# sapog_reference_hardware.net
KiCad netlist of a schematic drawn in EAGLE
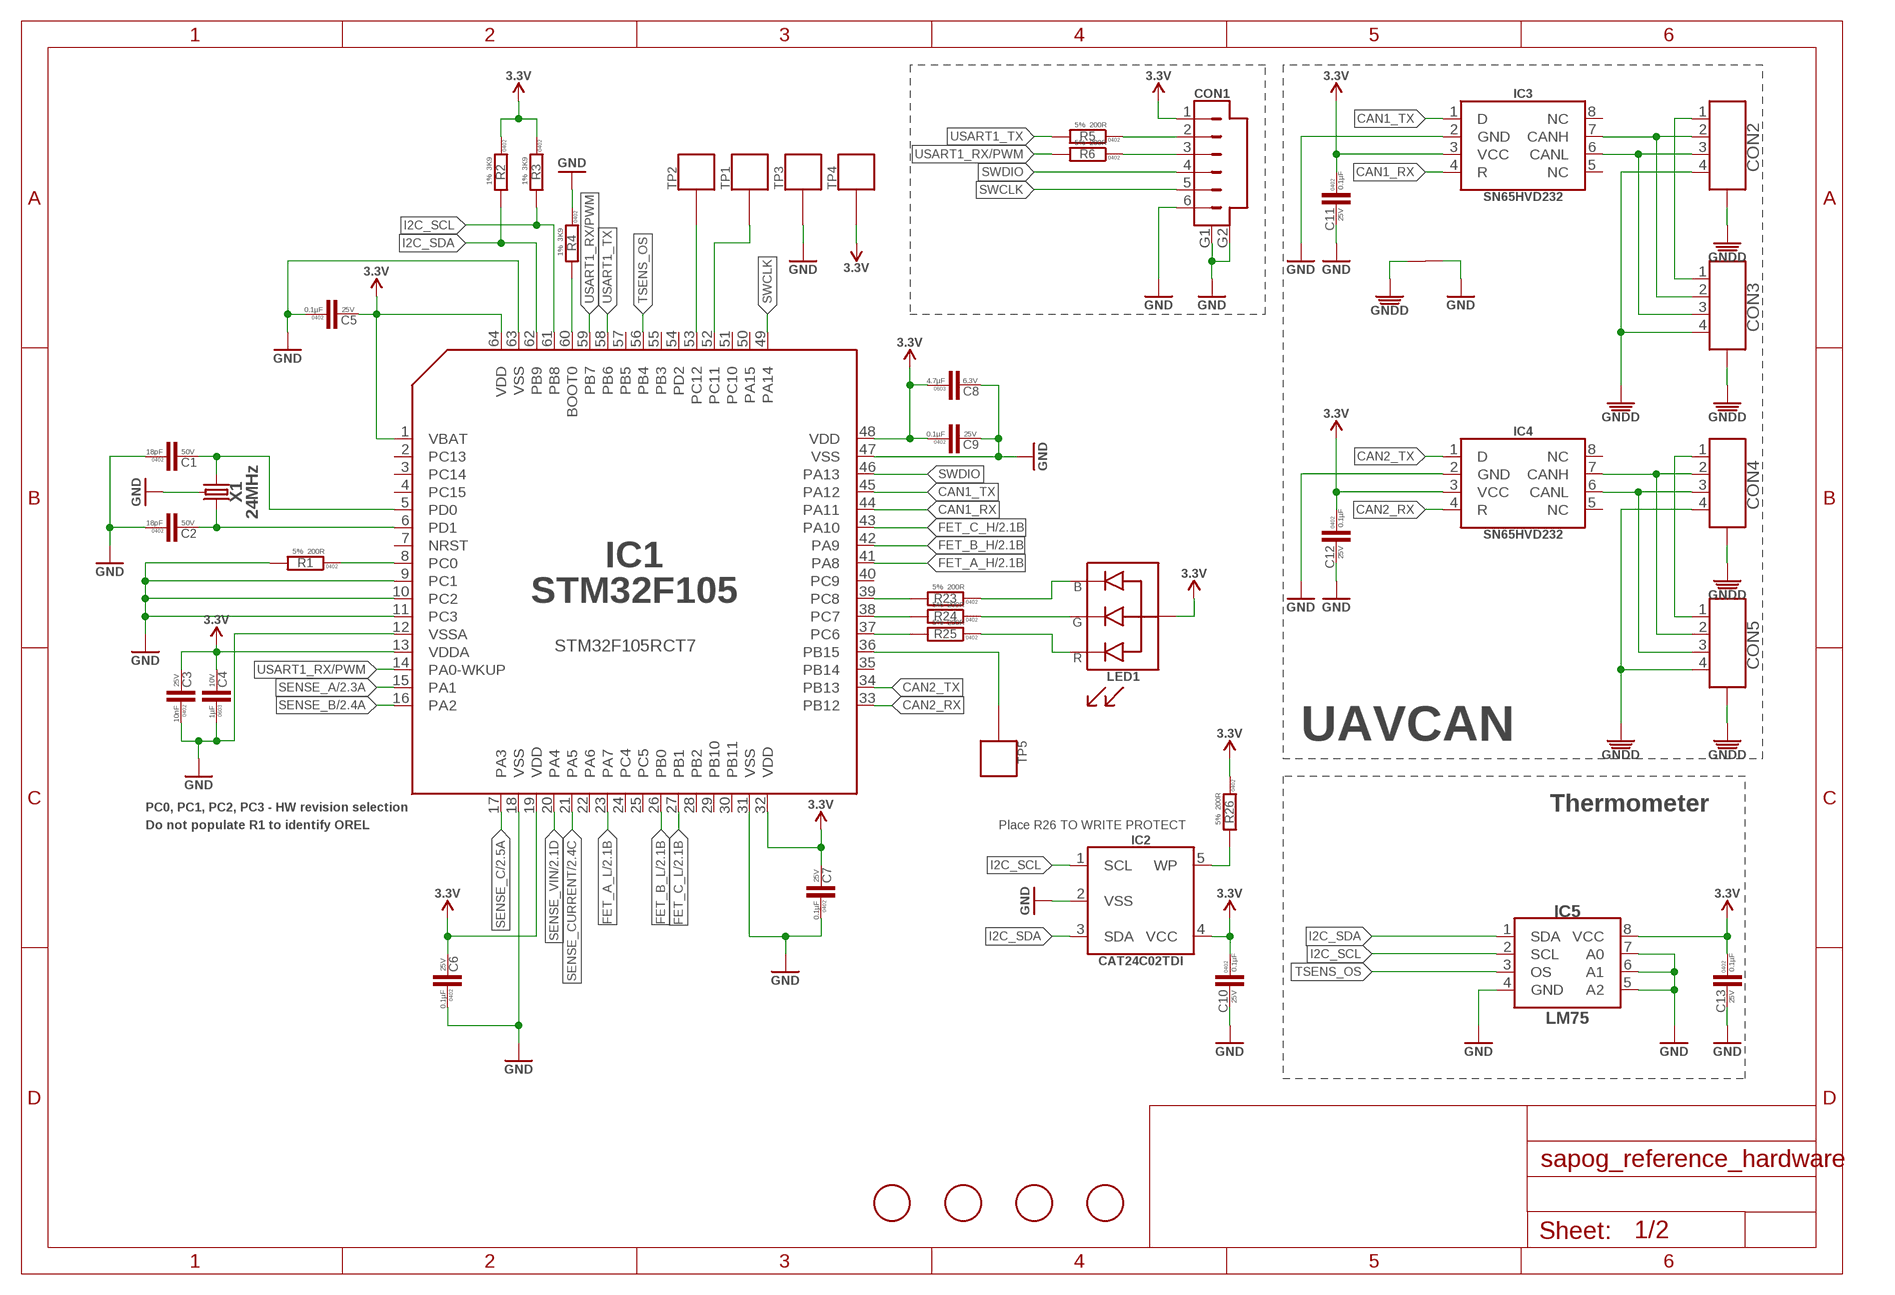
[diagram p0: schematic, sheet 1]
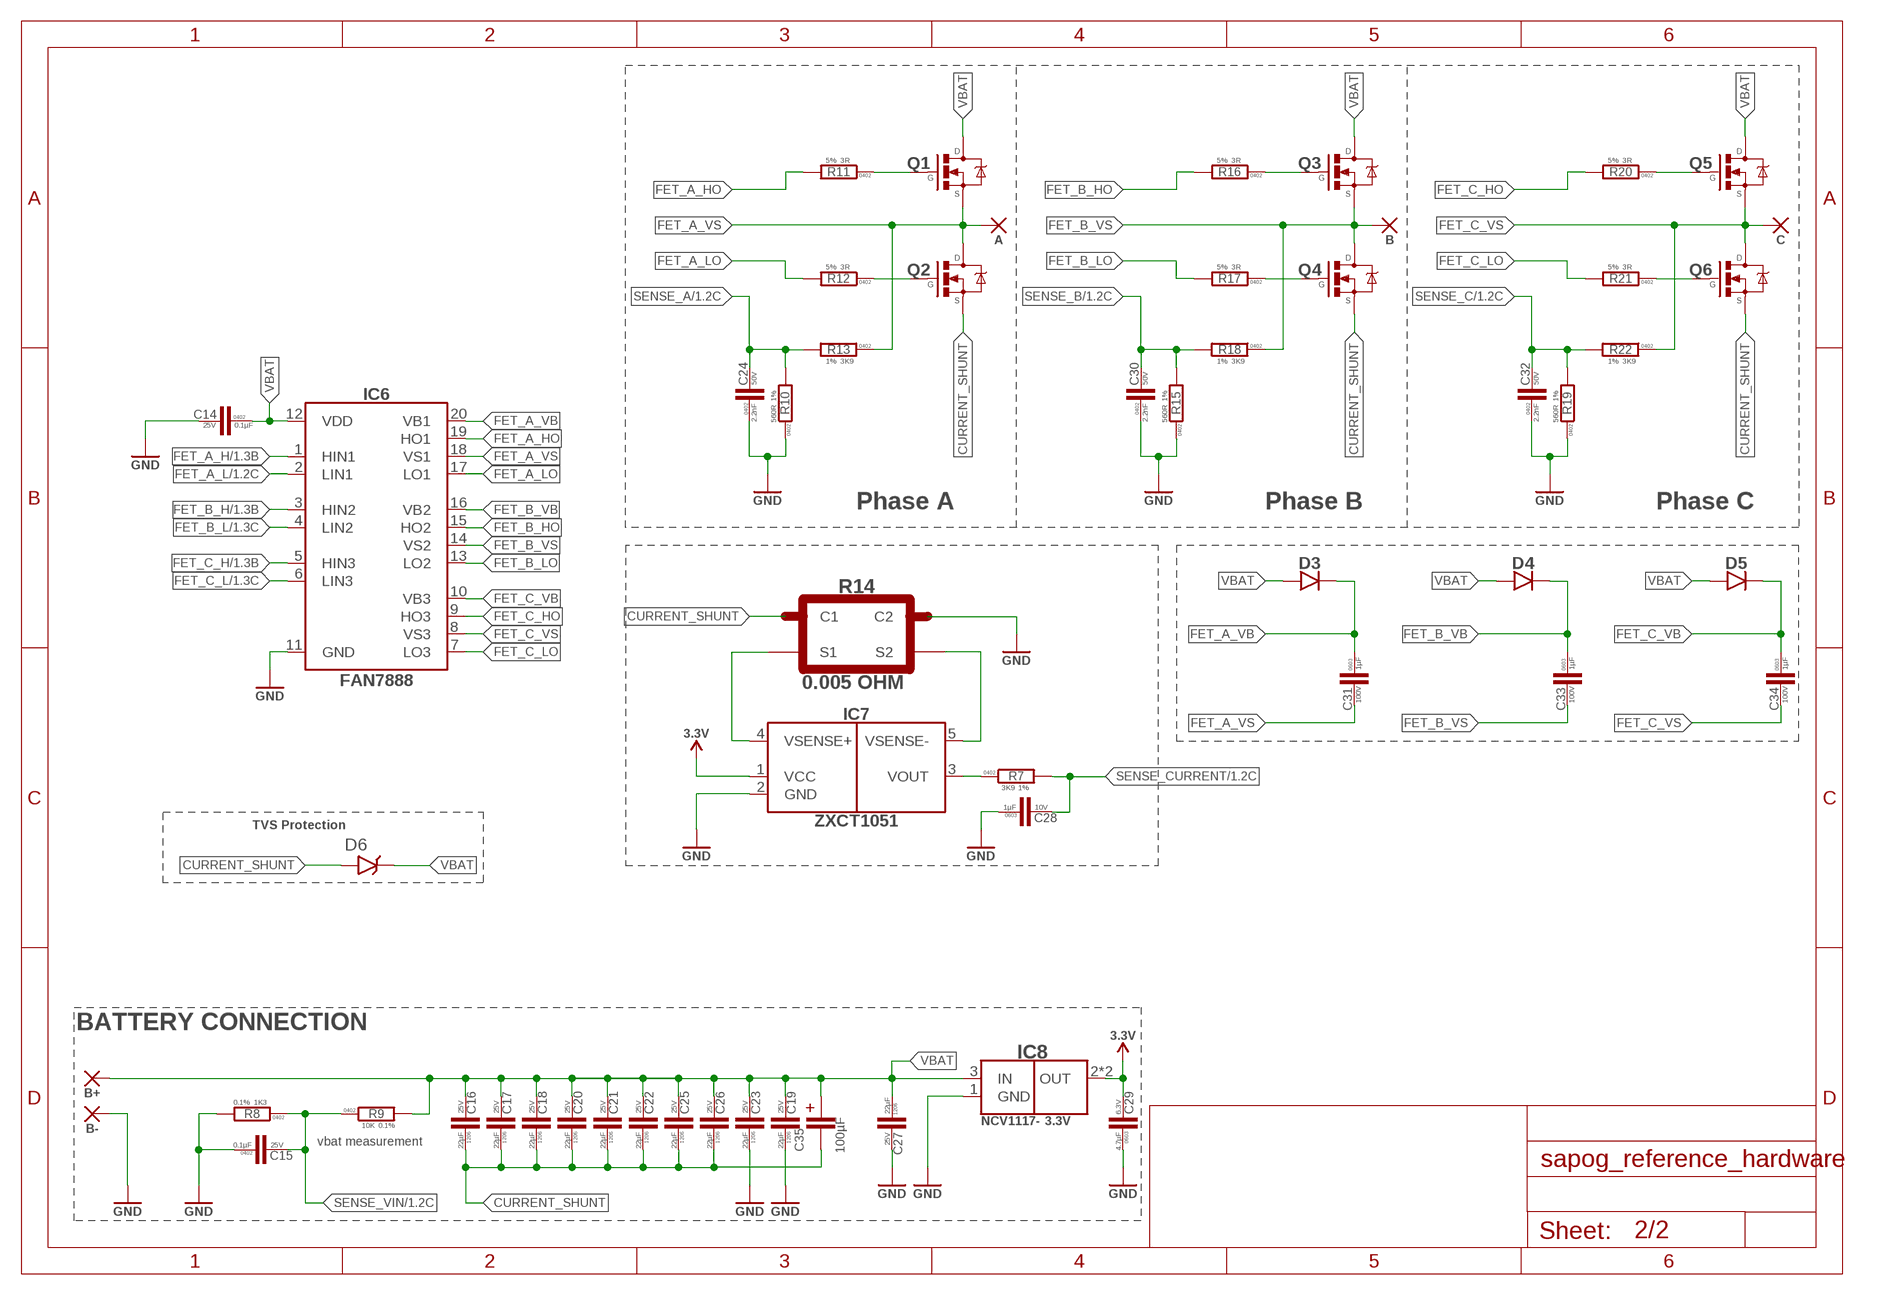
[diagram p1: schematic, sheet 2]

(export (version "E")
  (design (tool "Eeschema 10.0.6"))
  (components
    (comp (ref "C1")
      (value "18pF")
      (footprint "eagle-import:C0402")
      (fields (field (name "MANF") "Kemet") (field (name "TOLERANCE") "+-1%") (field (name "VOLTAGE") "50V"))
      (libsource (lib "eagle-import") (part "18PF-0402-50V_5%_NP0"))
    )
    (comp (ref "C2")
      (value "18pF")
      (footprint "eagle-import:C0402")
      (fields (field (name "MANF") "Kemet") (field (name "TOLERANCE") "+-1%") (field (name "VOLTAGE") "50V"))
      (libsource (lib "eagle-import") (part "18PF-0402-50V_5%_NP0"))
    )
    (comp (ref "C3")
      (value "10nF")
      (footprint "eagle-import:C0402")
      (fields
        (field (name "MANF") "Murata Electronics North America")
        (field (name "TOLERANCE") "+-10%")
        (field (name "VOLTAGE") "25V")
      )
      (libsource (lib "eagle-import") (part "10NF-0402-25V_10%_X7R"))
    )
    (comp (ref "C4")
      (value "1µF")
      (footprint "eagle-import:C0603")
      (fields
        (field (name "MANF") "Taiyo Yuden")
        (field (name "TOLERANCE") "+-10%")
        (field (name "VOLTAGE") "10V")
      )
      (libsource (lib "eagle-import") (part "1µF-0603-10V_10%_X7R"))
    )
    (comp (ref "C5")
      (value "0.1µF")
      (footprint "eagle-import:C0402")
      (fields
        (field (name "MANF") "TDK Corporation")
        (field (name "TOLERANCE") "+-20%")
        (field (name "VOLTAGE") "25V")
      )
      (libsource (lib "eagle-import") (part "0.1µF-0402-25V_20%_X6S"))
    )
    (comp (ref "C6")
      (value "0.1µF")
      (footprint "eagle-import:C0402")
      (fields
        (field (name "MANF") "TDK Corporation")
        (field (name "TOLERANCE") "+-20%")
        (field (name "VOLTAGE") "25V")
      )
      (libsource (lib "eagle-import") (part "0.1µF-0402-25V_20%_X6S"))
    )
    (comp (ref "C7")
      (value "0.1µF")
      (footprint "eagle-import:C0402")
      (fields
        (field (name "MANF") "TDK Corporation")
        (field (name "TOLERANCE") "+-20%")
        (field (name "VOLTAGE") "25V")
      )
      (libsource (lib "eagle-import") (part "0.1µF-0402-25V_20%_X6S"))
    )
    (comp (ref "C8")
      (value "4.7µF")
      (footprint "eagle-import:C0603")
      (fields
        (field (name "MANF") "Samsung Electro-Mechanics America")
        (field (name "TOLERANCE") "+-10%")
        (field (name "VOLTAGE") "6.3V")
      )
      (libsource (lib "eagle-import") (part "4.7µF-0603-6.3V_10%_X7R"))
    )
    (comp (ref "C9")
      (value "0.1µF")
      (footprint "eagle-import:C0402")
      (fields
        (field (name "MANF") "TDK Corporation")
        (field (name "TOLERANCE") "+-20%")
        (field (name "VOLTAGE") "25V")
      )
      (libsource (lib "eagle-import") (part "0.1µF-0402-25V_20%_X6S"))
    )
    (comp (ref "C10")
      (value "0.1µF")
      (footprint "eagle-import:C0402")
      (fields
        (field (name "MANF") "TDK Corporation")
        (field (name "TOLERANCE") "+-20%")
        (field (name "VOLTAGE") "25V")
      )
      (libsource (lib "eagle-import") (part "0.1µF-0402-25V_20%_X6S"))
    )
    (comp (ref "C11")
      (value "0.1µF")
      (footprint "eagle-import:C0402")
      (fields
        (field (name "MANF") "TDK Corporation")
        (field (name "TOLERANCE") "+-20%")
        (field (name "VOLTAGE") "25V")
      )
      (libsource (lib "eagle-import") (part "0.1µF-0402-25V_20%_X6S"))
    )
    (comp (ref "C12")
      (value "0.1µF")
      (footprint "eagle-import:C0402")
      (fields
        (field (name "MANF") "TDK Corporation")
        (field (name "TOLERANCE") "+-20%")
        (field (name "VOLTAGE") "25V")
      )
      (libsource (lib "eagle-import") (part "0.1µF-0402-25V_20%_X6S"))
    )
    (comp (ref "C13")
      (value "0.1µF")
      (footprint "eagle-import:C0402")
      (fields
        (field (name "MANF") "TDK Corporation")
        (field (name "TOLERANCE") "+-20%")
        (field (name "VOLTAGE") "25V")
      )
      (libsource (lib "eagle-import") (part "0.1µF-0402-25V_20%_X6S"))
    )
    (comp (ref "CON1")
      (value "SM06B-SRSS-TB")
      (footprint "eagle-import:SM06B")
      (fields (field (name "MANF") "JST Sales America Inc") (field (name "PARTNO") "SM06B-SRSS-TB"))
      (libsource (lib "eagle-import") (part "SM06B-SRSS-TB"))
    )
    (comp (ref "CON2")
      (value "CON-4P-RA-JST_GH")
      (footprint "eagle-import:JST_GH-4P-RA")
      (fields (field (name "MANF") "JST Sales America Inc"))
      (libsource (lib "eagle-import") (part "CON-4P-RA-JST_GH"))
    )
    (comp (ref "CON3")
      (value "CON-4P-RA-JST_GH")
      (footprint "eagle-import:JST_GH-4P-RA")
      (fields (field (name "MANF") "JST Sales America Inc"))
      (libsource (lib "eagle-import") (part "CON-4P-RA-JST_GH"))
    )
    (comp (ref "CON4")
      (value "CON-4P-RA-JST_GH")
      (footprint "eagle-import:JST_GH-4P-RA")
      (fields (field (name "MANF") "JST Sales America Inc"))
      (libsource (lib "eagle-import") (part "CON-4P-RA-JST_GH"))
    )
    (comp (ref "CON5")
      (value "CON-4P-RA-JST_GH")
      (footprint "eagle-import:JST_GH-4P-RA")
      (fields (field (name "MANF") "JST Sales America Inc"))
      (libsource (lib "eagle-import") (part "CON-4P-RA-JST_GH"))
    )
    (comp (ref "FD1")
      (value "FIDUCIALMOUNT")
      (footprint "eagle-import:FIDUCIA-MOUNT")
      (libsource (lib "eagle-import") (part "FIDUCIALMOUNT"))
    )
    (comp (ref "FD2")
      (value "FIDUCIALMOUNT")
      (footprint "eagle-import:FIDUCIA-MOUNT")
      (libsource (lib "eagle-import") (part "FIDUCIALMOUNT"))
    )
    (comp (ref "FD3")
      (value "FIDUCIALMOUNT")
      (footprint "eagle-import:FIDUCIA-MOUNT")
      (libsource (lib "eagle-import") (part "FIDUCIALMOUNT"))
    )
    (comp (ref "FD4")
      (value "FIDUCIALMOUNT")
      (footprint "eagle-import:FIDUCIA-MOUNT")
      (libsource (lib "eagle-import") (part "FIDUCIALMOUNT"))
    )
    (comp (ref "IC1")
      (value "STM32F105")
      (footprint "eagle-import:TQFP64-10X10")
      (fields
        (field (name "MANF") "STMicroelectronics")
        (field (name "DIGIKEY#") "497-11547-ND")
        (field (name "MANF#") "STM32F105RCT7")
      )
      (libsource (lib "eagle-import") (part "STM32F105"))
    )
    (comp (ref "IC2")
      (value "CAT24C02")
      (footprint "eagle-import:SOT23-5L")
      (fields (field (name "MANF") "ON Semiconductor"))
      (libsource (lib "eagle-import") (part "CAT24C02"))
    )
    (comp (ref "IC3")
      (value "SN65HVD232D")
      (footprint "eagle-import:SOIC8")
      (fields (field (name "MANF") "Texas Instruments"))
      (libsource (lib "eagle-import") (part "SN65HVD232D"))
    )
    (comp (ref "IC4")
      (value "SN65HVD232D")
      (footprint "eagle-import:SOIC8")
      (fields (field (name "MANF") "Texas Instruments"))
      (libsource (lib "eagle-import") (part "SN65HVD232D"))
    )
    (comp (ref "IC5")
      (value "LM75BD-TSSOP8")
      (footprint "eagle-import:TSSOP8")
      (fields (field (name "MANF") "NXP Semiconductors"))
      (libsource (lib "eagle-import") (part "LM75BD-TSSOP8"))
    )
    (comp (ref "LED1")
      (value "LTST-C19HE1WT")
      (footprint "eagle-import:LITE_ON_RGB_LED")
      (libsource (lib "eagle-import") (part "LTST-C19HE1WT"))
    )
    (comp (ref "R1")
      (value "200R")
      (footprint "eagle-import:R0402")
      (fields (field (name "MANF") "Yageo") (field (name "TOLERANCE") "5%"))
      (libsource (lib "eagle-import") (part "200R-0402-5%"))
    )
    (comp (ref "R2")
      (value "3K9")
      (footprint "eagle-import:R0402")
      (fields (field (name "MANF") "Yageo") (field (name "TOLERANCE") "1%"))
      (libsource (lib "eagle-import") (part "3K9-0402-1%"))
    )
    (comp (ref "R3")
      (value "3K9")
      (footprint "eagle-import:R0402")
      (fields (field (name "MANF") "Yageo") (field (name "TOLERANCE") "1%"))
      (libsource (lib "eagle-import") (part "3K9-0402-1%"))
    )
    (comp (ref "R4")
      (value "3K9")
      (footprint "eagle-import:R0402")
      (fields (field (name "MANF") "Yageo") (field (name "TOLERANCE") "1%"))
      (libsource (lib "eagle-import") (part "3K9-0402-1%"))
    )
    (comp (ref "R5")
      (value "200R")
      (footprint "eagle-import:R0402")
      (fields
        (field (name "MANF") "Yageo")
        (field (name "TOLERANCE") "5%")
        (field (name "PARTNO") "RC0402FR-07240RL")
      )
      (libsource (lib "eagle-import") (part "200R-0402-5%"))
    )
    (comp (ref "R6")
      (value "200R")
      (footprint "eagle-import:R0402")
      (fields
        (field (name "MANF") "Yageo")
        (field (name "TOLERANCE") "5%")
        (field (name "PARTNO") "RC0402FR-07240RL")
      )
      (libsource (lib "eagle-import") (part "200R-0402-5%"))
    )
    (comp (ref "R23")
      (value "200R")
      (footprint "eagle-import:R0402")
      (fields
        (field (name "MANF") "Yageo")
        (field (name "TOLERANCE") "5%")
        (field (name "PARTNO") "RC0402FR-07240RL")
      )
      (libsource (lib "eagle-import") (part "200R-0402-5%"))
    )
    (comp (ref "R24")
      (value "200R")
      (footprint "eagle-import:R0402")
      (fields
        (field (name "MANF") "Yageo")
        (field (name "TOLERANCE") "5%")
        (field (name "PARTNO") "RC0402FR-07240RL")
      )
      (libsource (lib "eagle-import") (part "200R-0402-5%"))
    )
    (comp (ref "R25")
      (value "200R")
      (footprint "eagle-import:R0402")
      (fields
        (field (name "MANF") "Yageo")
        (field (name "TOLERANCE") "5%")
        (field (name "PARTNO") "RC0402FR-07240RL")
      )
      (libsource (lib "eagle-import") (part "200R-0402-5%"))
    )
    (comp (ref "R26")
      (value "200R")
      (footprint "eagle-import:R0402")
      (fields
        (field (name "MANF") "Yageo")
        (field (name "TOLERANCE") "5%")
        (field (name "PARTNO") "RC0402FR-07240RL")
      )
      (libsource (lib "eagle-import") (part "200R-0402-5%"))
    )
    (comp (ref "TP1")
      (value "PAD.05")
      (footprint "eagle-import:PAD.05X.05")
      (libsource (lib "eagle-import") (part "PAD.05"))
    )
    (comp (ref "TP2")
      (value "PAD.05")
      (footprint "eagle-import:PAD.05X.05")
      (libsource (lib "eagle-import") (part "PAD.05"))
    )
    (comp (ref "TP3")
      (value "PAD.05")
      (footprint "eagle-import:PAD.05X.05")
      (libsource (lib "eagle-import") (part "PAD.05"))
    )
    (comp (ref "TP4")
      (value "PAD.05")
      (footprint "eagle-import:PAD.05X.05")
      (libsource (lib "eagle-import") (part "PAD.05"))
    )
    (comp (ref "TP5")
      (value "PAD.05")
      (footprint "eagle-import:PAD.05X.05")
      (libsource (lib "eagle-import") (part "PAD.05"))
    )
    (comp (ref "U$2")
      (value "CONNECTION")
      (footprint "eagle-import:CONNECTION")
      (libsource (lib "eagle-import") (part "CONNECTION"))
    )
    (comp (ref "X1")
      (value "24MHz")
      (footprint "eagle-import:OSCILLATOR-3.2X2.5")
      (fields
        (field (name "MANF") "AVX Corp/Kyocera Corp")
        (field (name "DIGIKEY#") "1253-1198-1-ND")
        (field (name "MANF#") "CX3225GB24000P0HPQCC")
      )
      (libsource (lib "eagle-import") (part "CRYSTAL-3.2X2.5-4P"))
    )
    (comp (ref "A")
      (value "WIREPADSMD5-2,5")
      (footprint "eagle-import:5-2,5")
      (libsource (lib "eagle-import") (part "WIREPADSMD5-2,5"))
    )
    (comp (ref "B")
      (value "WIREPADSMD5-2,5")
      (footprint "eagle-import:5-2,5")
      (libsource (lib "eagle-import") (part "WIREPADSMD5-2,5"))
    )
    (comp (ref "B+")
      (value "WIREPADSMD5-2,5")
      (footprint "eagle-import:5-2,5")
      (libsource (lib "eagle-import") (part "WIREPADSMD5-2,5"))
    )
    (comp (ref "B-")
      (value "WIREPADSMD5-2,5")
      (footprint "eagle-import:5-2,5")
      (libsource (lib "eagle-import") (part "WIREPADSMD5-2,5"))
    )
    (comp (ref "C")
      (value "WIREPADSMD5-2,5")
      (footprint "eagle-import:5-2,5")
      (libsource (lib "eagle-import") (part "WIREPADSMD5-2,5"))
    )
    (comp (ref "C14")
      (value "0.1µF")
      (footprint "eagle-import:C0402")
      (fields
        (field (name "MANF") "TDK Corporation")
        (field (name "TOLERANCE") "+-20%")
        (field (name "VOLTAGE") "25V")
      )
      (libsource (lib "eagle-import") (part "0.1µF-0402-25V_20%_X6S"))
    )
    (comp (ref "C15")
      (value "0.1µF")
      (footprint "eagle-import:C0402")
      (fields
        (field (name "MANF") "TDK Corporation")
        (field (name "TOLERANCE") "+-20%")
        (field (name "VOLTAGE") "25V")
      )
      (libsource (lib "eagle-import") (part "0.1µF-0402-25V_20%_X6S"))
    )
    (comp (ref "C16")
      (value "22µF")
      (footprint "eagle-import:C1206")
      (fields
        (field (name "MANF") "Samsung Electro-Mechanics America")
        (field (name "TOLERANCE") "+-10%")
        (field (name "VOLTAGE") "25V")
      )
      (libsource (lib "eagle-import") (part "22µF-1206-25V_10%_X6S"))
    )
    (comp (ref "C17")
      (value "22µF")
      (footprint "eagle-import:C1206")
      (fields
        (field (name "MANF") "Samsung Electro-Mechanics America")
        (field (name "TOLERANCE") "+-10%")
        (field (name "VOLTAGE") "25V")
      )
      (libsource (lib "eagle-import") (part "22µF-1206-25V_10%_X6S"))
    )
    (comp (ref "C18")
      (value "22µF")
      (footprint "eagle-import:C1206")
      (fields
        (field (name "MANF") "Samsung Electro-Mechanics America")
        (field (name "TOLERANCE") "+-10%")
        (field (name "VOLTAGE") "25V")
      )
      (libsource (lib "eagle-import") (part "22µF-1206-25V_10%_X6S"))
    )
    (comp (ref "C19")
      (value "22µF")
      (footprint "eagle-import:C1206")
      (fields
        (field (name "MANF") "Samsung Electro-Mechanics America")
        (field (name "TOLERANCE") "+-10%")
        (field (name "VOLTAGE") "25V")
      )
      (libsource (lib "eagle-import") (part "22µF-1206-25V_10%_X6S"))
    )
    (comp (ref "C20")
      (value "22µF")
      (footprint "eagle-import:C1206")
      (fields
        (field (name "MANF") "Samsung Electro-Mechanics America")
        (field (name "TOLERANCE") "+-10%")
        (field (name "VOLTAGE") "25V")
      )
      (libsource (lib "eagle-import") (part "22µF-1206-25V_10%_X6S"))
    )
    (comp (ref "C21")
      (value "22µF")
      (footprint "eagle-import:C1206")
      (fields
        (field (name "MANF") "Samsung Electro-Mechanics America")
        (field (name "TOLERANCE") "+-10%")
        (field (name "VOLTAGE") "25V")
      )
      (libsource (lib "eagle-import") (part "22µF-1206-25V_10%_X6S"))
    )
    (comp (ref "C22")
      (value "22µF")
      (footprint "eagle-import:C1206")
      (fields
        (field (name "MANF") "Samsung Electro-Mechanics America")
        (field (name "TOLERANCE") "+-10%")
        (field (name "VOLTAGE") "25V")
      )
      (libsource (lib "eagle-import") (part "22µF-1206-25V_10%_X6S"))
    )
    (comp (ref "C23")
      (value "22µF")
      (footprint "eagle-import:C1206")
      (fields
        (field (name "MANF") "Samsung Electro-Mechanics America")
        (field (name "TOLERANCE") "+-10%")
        (field (name "VOLTAGE") "25V")
      )
      (libsource (lib "eagle-import") (part "22µF-1206-25V_10%_X6S"))
    )
    (comp (ref "C24")
      (value "2.2nF")
      (footprint "eagle-import:C0402")
      (fields
        (field (name "MANF") "AVX Corporation")
        (field (name "TOLERANCE") "+-10%")
        (field (name "VOLTAGE") "50V")
      )
      (libsource (lib "eagle-import") (part "2.2NF-0402-50V_10%_X7R"))
    )
    (comp (ref "C25")
      (value "22µF")
      (footprint "eagle-import:C1206")
      (fields
        (field (name "MANF") "Samsung Electro-Mechanics America")
        (field (name "TOLERANCE") "+-10%")
        (field (name "VOLTAGE") "25V")
      )
      (libsource (lib "eagle-import") (part "22µF-1206-25V_10%_X6S"))
    )
    (comp (ref "C26")
      (value "22µF")
      (footprint "eagle-import:C1206")
      (fields
        (field (name "MANF") "Samsung Electro-Mechanics America")
        (field (name "TOLERANCE") "+-10%")
        (field (name "VOLTAGE") "25V")
      )
      (libsource (lib "eagle-import") (part "22µF-1206-25V_10%_X6S"))
    )
    (comp (ref "C27")
      (value "22µF")
      (footprint "eagle-import:C1206")
      (fields
        (field (name "MANF") "Samsung Electro-Mechanics America")
        (field (name "TOLERANCE") "+-10%")
        (field (name "VOLTAGE") "25V")
      )
      (libsource (lib "eagle-import") (part "22µF-1206-25V_10%_X6S"))
    )
    (comp (ref "C28")
      (value "1µF")
      (footprint "eagle-import:C0603")
      (fields
        (field (name "MANF") "Taiyo Yuden")
        (field (name "TOLERANCE") "+-10%")
        (field (name "VOLTAGE") "10V")
      )
      (libsource (lib "eagle-import") (part "1µF-0603-10V_10%_X7R"))
    )
    (comp (ref "C29")
      (value "4.7µF")
      (footprint "eagle-import:C0603")
      (fields
        (field (name "MANF") "Samsung Electro-Mechanics America")
        (field (name "TOLERANCE") "+-10%")
        (field (name "VOLTAGE") "6.3V")
      )
      (libsource (lib "eagle-import") (part "4.7µF-0603-6.3V_10%_X7R"))
    )
    (comp (ref "C30")
      (value "2.2nF")
      (footprint "eagle-import:C0402")
      (fields
        (field (name "MANF") "AVX Corporation")
        (field (name "TOLERANCE") "+-10%")
        (field (name "VOLTAGE") "50V")
      )
      (libsource (lib "eagle-import") (part "2.2NF-0402-50V_10%_X7R"))
    )
    (comp (ref "C31")
      (value "1µF")
      (footprint "eagle-import:C0603")
      (fields
        (field (name "MANF") " TDK Corporation")
        (field (name "TOLERANCE") "+-10%")
        (field (name "VOLTAGE") "100V")
      )
      (libsource (lib "eagle-import") (part "1µF-0603-100V_10%_X7S"))
    )
    (comp (ref "C32")
      (value "2.2nF")
      (footprint "eagle-import:C0402")
      (fields
        (field (name "MANF") "AVX Corporation")
        (field (name "TOLERANCE") "+-10%")
        (field (name "VOLTAGE") "50V")
      )
      (libsource (lib "eagle-import") (part "2.2NF-0402-50V_10%_X7R"))
    )
    (comp (ref "C33")
      (value "1µF")
      (footprint "eagle-import:C0603")
      (fields
        (field (name "MANF") " TDK Corporation")
        (field (name "TOLERANCE") "+-10%")
        (field (name "VOLTAGE") "100V")
      )
      (libsource (lib "eagle-import") (part "1µF-0603-100V_10%_X7S"))
    )
    (comp (ref "C34")
      (value "1µF")
      (footprint "eagle-import:C0603")
      (fields
        (field (name "MANF") " TDK Corporation")
        (field (name "TOLERANCE") "+-10%")
        (field (name "VOLTAGE") "100V")
      )
      (libsource (lib "eagle-import") (part "1µF-0603-100V_10%_X7S"))
    )
    (comp (ref "C35")
      (value "100µF")
      (footprint "eagle-import:3024")
      (fields (field (name "MANF") "Vishay Sprague") (field (name "VOLTAGE") "35V"))
      (libsource (lib "eagle-import") (part "C-TANT-3024"))
    )
    (comp (ref "D3")
      (value "BAS21AHT1G")
      (footprint "eagle-import:SOD323")
      (fields (field (name "MANF") "ON Semiconductor"))
      (libsource (lib "eagle-import") (part "BAS21AHT1G"))
    )
    (comp (ref "D4")
      (value "BAS21AHT1G")
      (footprint "eagle-import:SOD323")
      (fields (field (name "MANF") "ON Semiconductor"))
      (libsource (lib "eagle-import") (part "BAS21AHT1G"))
    )
    (comp (ref "D5")
      (value "BAS21AHT1G")
      (footprint "eagle-import:SOD323")
      (fields (field (name "MANF") "ON Semiconductor"))
      (libsource (lib "eagle-import") (part "BAS21AHT1G"))
    )
    (comp (ref "D6")
      (value "1KSMB20A")
      (footprint "eagle-import:SMB")
      (fields (field (name "MANF") "Littelfuse Inc"))
      (libsource (lib "eagle-import") (part "1KSMB20A"))
    )
    (comp (ref "IC6")
      (value "FAN7888")
      (footprint "eagle-import:SOIC20")
      (fields (field (name "MANF") "Fairchild Semiconductor") (field (name "PARTNO") "FAN7888MX"))
      (libsource (lib "eagle-import") (part "FAN7888"))
    )
    (comp (ref "IC7")
      (value "ZXCT1051")
      (footprint "eagle-import:SOT23-5L")
      (fields (field (name "MANF") "Diodes Incorporated"))
      (libsource (lib "eagle-import") (part "ZXCT1051"))
    )
    (comp (ref "IC8")
      (value "3.3V")
      (footprint "eagle-import:SOT-223")
      (fields (field (name "MANF") "ON Semiconductor"))
      (libsource (lib "eagle-import") (part "NCV1117-3.3"))
    )
    (comp (ref "Q1")
      (value "BSC019N04NS-DFN5X6")
      (footprint "eagle-import:DFN5X6")
      (fields (field (name "MANF") "Infineon Technologies"))
      (libsource (lib "eagle-import") (part "BSC019N04NS-DFN5X6"))
    )
    (comp (ref "Q2")
      (value "BSC019N04NS-DFN5X6")
      (footprint "eagle-import:DFN5X6")
      (fields (field (name "MANF") "Infineon Technologies"))
      (libsource (lib "eagle-import") (part "BSC019N04NS-DFN5X6"))
    )
    (comp (ref "Q3")
      (value "BSC019N04NS-DFN5X6")
      (footprint "eagle-import:DFN5X6")
      (fields (field (name "MANF") "Infineon Technologies"))
      (libsource (lib "eagle-import") (part "BSC019N04NS-DFN5X6"))
    )
    (comp (ref "Q4")
      (value "BSC019N04NS-DFN5X6")
      (footprint "eagle-import:DFN5X6")
      (fields (field (name "MANF") "Infineon Technologies"))
      (libsource (lib "eagle-import") (part "BSC019N04NS-DFN5X6"))
    )
    (comp (ref "Q5")
      (value "BSC019N04NS-DFN5X6")
      (footprint "eagle-import:DFN5X6")
      (fields (field (name "MANF") "Infineon Technologies"))
      (libsource (lib "eagle-import") (part "BSC019N04NS-DFN5X6"))
    )
    (comp (ref "Q6")
      (value "BSC019N04NS-DFN5X6")
      (footprint "eagle-import:DFN5X6")
      (fields (field (name "MANF") "Infineon Technologies"))
      (libsource (lib "eagle-import") (part "BSC019N04NS-DFN5X6"))
    )
    (comp (ref "R7")
      (value "3K9")
      (footprint "eagle-import:R0402")
      (fields (field (name "MANF") "Yageo") (field (name "TOLERANCE") "1%"))
      (libsource (lib "eagle-import") (part "3K9-0402-1%"))
    )
    (comp (ref "R8")
      (value "1K3")
      (footprint "eagle-import:R0402")
      (fields (field (name "MANF") "Panasonic Electronic Components") (field (name "TOLERANCE") "0.1%"))
      (libsource (lib "eagle-import") (part "1K3-0402-0.1%"))
    )
    (comp (ref "R9")
      (value "10K")
      (footprint "eagle-import:R0402")
      (fields (field (name "MANF") "Panasonic Electronic Components") (field (name "TOLERANCE") "0.1%"))
      (libsource (lib "eagle-import") (part "10K-0402-0.1%"))
    )
    (comp (ref "R10")
      (value "560R")
      (footprint "eagle-import:R0402")
      (fields (field (name "MANF") "Vishay Dale") (field (name "TOLERANCE") "1%"))
      (libsource (lib "eagle-import") (part "560R-0402-1%"))
    )
    (comp (ref "R11")
      (value "3R")
      (footprint "eagle-import:R0402")
      (fields (field (name "MANF") "Panasonic Electronic Components") (field (name "TOLERANCE") "5%"))
      (libsource (lib "eagle-import") (part "3R-0402-5%"))
    )
    (comp (ref "R12")
      (value "3R")
      (footprint "eagle-import:R0402")
      (fields (field (name "MANF") "Panasonic Electronic Components") (field (name "TOLERANCE") "5%"))
      (libsource (lib "eagle-import") (part "3R-0402-5%"))
    )
    (comp (ref "R13")
      (value "3K9")
      (footprint "eagle-import:R0402")
      (fields (field (name "MANF") "Yageo") (field (name "TOLERANCE") "1%"))
      (libsource (lib "eagle-import") (part "3K9-0402-1%"))
    )
    (comp (ref "R14")
      (value "0.005 OHM")
      (footprint "eagle-import:2010_CURRENT_SHUNT")
      (fields
        (field (name "MANF") "Stackpole Electronics Inc")
        (field (name "POWER") "1.5W")
        (field (name "TOLERANCE") "1%")
      )
      (libsource (lib "eagle-import") (part "CURRENT_SHUNT-CSNL2010"))
    )
    (comp (ref "R15")
      (value "560R")
      (footprint "eagle-import:R0402")
      (fields (field (name "MANF") "Vishay Dale") (field (name "TOLERANCE") "1%"))
      (libsource (lib "eagle-import") (part "560R-0402-1%"))
    )
    (comp (ref "R16")
      (value "3R")
      (footprint "eagle-import:R0402")
      (fields (field (name "MANF") "Panasonic Electronic Components") (field (name "TOLERANCE") "5%"))
      (libsource (lib "eagle-import") (part "3R-0402-5%"))
    )
    (comp (ref "R17")
      (value "3R")
      (footprint "eagle-import:R0402")
      (fields (field (name "MANF") "Panasonic Electronic Components") (field (name "TOLERANCE") "5%"))
      (libsource (lib "eagle-import") (part "3R-0402-5%"))
    )
    (comp (ref "R18")
      (value "3K9")
      (footprint "eagle-import:R0402")
      (fields (field (name "MANF") "Yageo") (field (name "TOLERANCE") "1%"))
      (libsource (lib "eagle-import") (part "3K9-0402-1%"))
    )
    (comp (ref "R19")
      (value "560R")
      (footprint "eagle-import:R0402")
      (fields (field (name "MANF") "Vishay Dale") (field (name "TOLERANCE") "1%"))
      (libsource (lib "eagle-import") (part "560R-0402-1%"))
    )
    (comp (ref "R20")
      (value "3R")
      (footprint "eagle-import:R0402")
      (fields (field (name "MANF") "Panasonic Electronic Components") (field (name "TOLERANCE") "5%"))
      (libsource (lib "eagle-import") (part "3R-0402-5%"))
    )
    (comp (ref "R21")
      (value "3R")
      (footprint "eagle-import:R0402")
      (fields (field (name "MANF") "Panasonic Electronic Components") (field (name "TOLERANCE") "5%"))
      (libsource (lib "eagle-import") (part "3R-0402-5%"))
    )
    (comp (ref "R22")
      (value "3K9")
      (footprint "eagle-import:R0402")
      (fields (field (name "MANF") "Yageo") (field (name "TOLERANCE") "1%"))
      (libsource (lib "eagle-import") (part "3K9-0402-1%"))
    )
  )
  (nets
    (net (code "1") (name "CAN1_RX") (class "Default")
      (node (ref "IC1") (pin "44") (pinfunction "PA11_44") (pintype "bidirectional"))
      (node (ref "IC3") (pin "4") (pinfunction "R_4") (pintype "bidirectional"))
    )
    (net (code "2") (name "CAN1_TX") (class "Default")
      (node (ref "IC1") (pin "45") (pinfunction "PA12_45") (pintype "bidirectional"))
      (node (ref "IC3") (pin "1") (pinfunction "D_1") (pintype "bidirectional"))
    )
    (net (code "3") (name "CAN2_RX") (class "Default")
      (node (ref "IC1") (pin "33") (pinfunction "PB12_33") (pintype "bidirectional"))
      (node (ref "IC4") (pin "4") (pinfunction "R_4") (pintype "bidirectional"))
    )
    (net (code "4") (name "CAN2_TX") (class "Default")
      (node (ref "IC1") (pin "34") (pinfunction "PB13_34") (pintype "bidirectional"))
      (node (ref "IC4") (pin "1") (pinfunction "D_1") (pintype "bidirectional"))
    )
    (net (code "5") (name "CURRENT_SHUNT") (class "Default")
      (node (ref "C16") (pin "P$1") (pinfunction "1_P$1") (pintype "passive"))
      (node (ref "C17") (pin "P$1") (pinfunction "1_P$1") (pintype "passive"))
      (node (ref "C18") (pin "P$1") (pinfunction "1_P$1") (pintype "passive"))
      (node (ref "C20") (pin "P$1") (pinfunction "1_P$1") (pintype "passive"))
      (node (ref "C21") (pin "P$1") (pinfunction "1_P$1") (pintype "passive"))
      (node (ref "C22") (pin "P$1") (pinfunction "1_P$1") (pintype "passive"))
      (node (ref "C25") (pin "P$1") (pinfunction "1_P$1") (pintype "passive"))
      (node (ref "C26") (pin "P$1") (pinfunction "1_P$1") (pintype "passive"))
      (node (ref "C35") (pin "-") (pinfunction "-_-") (pintype "passive"))
      (node (ref "D6") (pin "A") (pinfunction "A_A") (pintype "bidirectional"))
      (node (ref "Q2") (pin "1S") (pinfunction "S_1S") (pintype "passive"))
      (node (ref "Q2") (pin "2S") (pinfunction "S_2S") (pintype "passive"))
      (node (ref "Q2") (pin "3S") (pinfunction "S_3S") (pintype "passive"))
      (node (ref "Q4") (pin "1S") (pinfunction "S_1S") (pintype "passive"))
      (node (ref "Q4") (pin "2S") (pinfunction "S_2S") (pintype "passive"))
      (node (ref "Q4") (pin "3S") (pinfunction "S_3S") (pintype "passive"))
      (node (ref "Q6") (pin "1S") (pinfunction "S_1S") (pintype "passive"))
      (node (ref "Q6") (pin "2S") (pinfunction "S_2S") (pintype "passive"))
      (node (ref "Q6") (pin "3S") (pinfunction "S_3S") (pintype "passive"))
      (node (ref "R14") (pin "CURRENT1") (pinfunction "C1_CURRENT1") (pintype "bidirectional"))
    )
    (net (code "6") (name "FET_A_H") (class "Default")
      (node (ref "IC1") (pin "41") (pinfunction "PA8_41") (pintype "bidirectional"))
      (node (ref "IC6") (pin "1") (pinfunction "HIN1_1") (pintype "bidirectional"))
    )
    (net (code "7") (name "FET_A_HO") (class "Default")
      (node (ref "IC6") (pin "19") (pinfunction "HO1_19") (pintype "bidirectional"))
      (node (ref "R11") (pin "2") (pinfunction "2_2") (pintype "passive"))
    )
    (net (code "8") (name "FET_A_L") (class "Default")
      (node (ref "IC1") (pin "23") (pinfunction "PA7_23") (pintype "bidirectional"))
      (node (ref "IC6") (pin "2") (pinfunction "LIN1_2") (pintype "bidirectional"))
    )
    (net (code "9") (name "FET_A_LO") (class "Default")
      (node (ref "IC6") (pin "17") (pinfunction "LO1_17") (pintype "bidirectional"))
      (node (ref "R12") (pin "2") (pinfunction "2_2") (pintype "passive"))
    )
    (net (code "10") (name "FET_A_VB") (class "Default")
      (node (ref "C31") (pin "P$1") (pinfunction "1_P$1") (pintype "passive"))
      (node (ref "D3") (pin "C") (pinfunction "C_C") (pintype "passive"))
      (node (ref "IC6") (pin "20") (pinfunction "VB1_20") (pintype "bidirectional"))
    )
    (net (code "11") (name "FET_A_VS") (class "Default")
      (node (ref "A") (pin "1") (pinfunction "P_1") (pintype "passive"))
      (node (ref "C31") (pin "P$2") (pinfunction "2_P$2") (pintype "passive"))
      (node (ref "IC6") (pin "18") (pinfunction "VS1_18") (pintype "bidirectional"))
      (node (ref "Q1") (pin "1S") (pinfunction "S_1S") (pintype "passive"))
      (node (ref "Q1") (pin "2S") (pinfunction "S_2S") (pintype "passive"))
      (node (ref "Q1") (pin "3S") (pinfunction "S_3S") (pintype "passive"))
      (node (ref "Q2") (pin "5D") (pinfunction "D_5D") (pintype "passive"))
      (node (ref "Q2") (pin "6D") (pinfunction "D_6D") (pintype "passive"))
      (node (ref "Q2") (pin "7D") (pinfunction "D_7D") (pintype "passive"))
      (node (ref "Q2") (pin "8D") (pinfunction "D_8D") (pintype "passive"))
      (node (ref "R13") (pin "1") (pinfunction "1_1") (pintype "passive"))
    )
    (net (code "12") (name "FET_B_H") (class "Default")
      (node (ref "IC1") (pin "42") (pinfunction "PA9_42") (pintype "bidirectional"))
      (node (ref "IC6") (pin "3") (pinfunction "HIN2_3") (pintype "bidirectional"))
    )
    (net (code "13") (name "FET_B_HO") (class "Default")
      (node (ref "IC6") (pin "15") (pinfunction "HO2_15") (pintype "bidirectional"))
      (node (ref "R16") (pin "2") (pinfunction "2_2") (pintype "passive"))
    )
    (net (code "14") (name "FET_B_L") (class "Default")
      (node (ref "IC1") (pin "26") (pinfunction "PB0_26") (pintype "bidirectional"))
      (node (ref "IC6") (pin "4") (pinfunction "LIN2_4") (pintype "bidirectional"))
    )
    (net (code "15") (name "FET_B_LO") (class "Default")
      (node (ref "IC6") (pin "13") (pinfunction "LO2_13") (pintype "bidirectional"))
      (node (ref "R17") (pin "2") (pinfunction "2_2") (pintype "passive"))
    )
    (net (code "16") (name "FET_B_VB") (class "Default")
      (node (ref "C33") (pin "P$1") (pinfunction "1_P$1") (pintype "passive"))
      (node (ref "D4") (pin "C") (pinfunction "C_C") (pintype "passive"))
      (node (ref "IC6") (pin "16") (pinfunction "VB2_16") (pintype "bidirectional"))
    )
    (net (code "17") (name "FET_B_VS") (class "Default")
      (node (ref "B") (pin "1") (pinfunction "P_1") (pintype "passive"))
      (node (ref "C33") (pin "P$2") (pinfunction "2_P$2") (pintype "passive"))
      (node (ref "IC6") (pin "14") (pinfunction "VS2_14") (pintype "bidirectional"))
      (node (ref "Q3") (pin "1S") (pinfunction "S_1S") (pintype "passive"))
      (node (ref "Q3") (pin "2S") (pinfunction "S_2S") (pintype "passive"))
      (node (ref "Q3") (pin "3S") (pinfunction "S_3S") (pintype "passive"))
      (node (ref "Q4") (pin "5D") (pinfunction "D_5D") (pintype "passive"))
      (node (ref "Q4") (pin "6D") (pinfunction "D_6D") (pintype "passive"))
      (node (ref "Q4") (pin "7D") (pinfunction "D_7D") (pintype "passive"))
      (node (ref "Q4") (pin "8D") (pinfunction "D_8D") (pintype "passive"))
      (node (ref "R18") (pin "1") (pinfunction "1_1") (pintype "passive"))
    )
    (net (code "18") (name "FET_C_H") (class "Default")
      (node (ref "IC1") (pin "43") (pinfunction "PA10_43") (pintype "bidirectional"))
      (node (ref "IC6") (pin "5") (pinfunction "HIN3_5") (pintype "bidirectional"))
    )
    (net (code "19") (name "FET_C_HO") (class "Default")
      (node (ref "IC6") (pin "9") (pinfunction "HO3_9") (pintype "bidirectional"))
      (node (ref "R20") (pin "2") (pinfunction "2_2") (pintype "passive"))
    )
    (net (code "20") (name "FET_C_L") (class "Default")
      (node (ref "IC1") (pin "27") (pinfunction "PB1_27") (pintype "bidirectional"))
      (node (ref "IC6") (pin "6") (pinfunction "LIN3_6") (pintype "bidirectional"))
    )
    (net (code "21") (name "FET_C_LO") (class "Default")
      (node (ref "IC6") (pin "7") (pinfunction "LO3_7") (pintype "bidirectional"))
      (node (ref "R21") (pin "2") (pinfunction "2_2") (pintype "passive"))
    )
    (net (code "22") (name "FET_C_VB") (class "Default")
      (node (ref "C34") (pin "P$1") (pinfunction "1_P$1") (pintype "passive"))
      (node (ref "D5") (pin "C") (pinfunction "C_C") (pintype "passive"))
      (node (ref "IC6") (pin "10") (pinfunction "VB3_10") (pintype "bidirectional"))
    )
    (net (code "23") (name "FET_C_VS") (class "Default")
      (node (ref "C") (pin "1") (pinfunction "P_1") (pintype "passive"))
      (node (ref "C34") (pin "P$2") (pinfunction "2_P$2") (pintype "passive"))
      (node (ref "IC6") (pin "8") (pinfunction "VS3_8") (pintype "bidirectional"))
      (node (ref "Q5") (pin "1S") (pinfunction "S_1S") (pintype "passive"))
      (node (ref "Q5") (pin "2S") (pinfunction "S_2S") (pintype "passive"))
      (node (ref "Q5") (pin "3S") (pinfunction "S_3S") (pintype "passive"))
      (node (ref "Q6") (pin "5D") (pinfunction "D_5D") (pintype "passive"))
      (node (ref "Q6") (pin "6D") (pinfunction "D_6D") (pintype "passive"))
      (node (ref "Q6") (pin "7D") (pinfunction "D_7D") (pintype "passive"))
      (node (ref "Q6") (pin "8D") (pinfunction "D_8D") (pintype "passive"))
      (node (ref "R22") (pin "1") (pinfunction "1_1") (pintype "passive"))
    )
    (net (code "24") (name "GND") (class "Default")
      (node (ref "B-") (pin "1") (pinfunction "P_1") (pintype "passive"))
      (node (ref "C1") (pin "1") (pinfunction "1_1") (pintype "passive"))
      (node (ref "C10") (pin "2") (pinfunction "2_2") (pintype "passive"))
      (node (ref "C11") (pin "2") (pinfunction "2_2") (pintype "passive"))
      (node (ref "C12") (pin "2") (pinfunction "2_2") (pintype "passive"))
      (node (ref "C13") (pin "2") (pinfunction "2_2") (pintype "passive"))
      (node (ref "C14") (pin "2") (pinfunction "2_2") (pintype "passive"))
      (node (ref "C15") (pin "1") (pinfunction "1_1") (pintype "passive"))
      (node (ref "C19") (pin "P$1") (pinfunction "1_P$1") (pintype "passive"))
      (node (ref "C2") (pin "1") (pinfunction "1_1") (pintype "passive"))
      (node (ref "C23") (pin "P$1") (pinfunction "1_P$1") (pintype "passive"))
      (node (ref "C24") (pin "1") (pinfunction "1_1") (pintype "passive"))
      (node (ref "C27") (pin "P$2") (pinfunction "2_P$2") (pintype "passive"))
      (node (ref "C28") (pin "P$1") (pinfunction "1_P$1") (pintype "passive"))
      (node (ref "C29") (pin "P$1") (pinfunction "1_P$1") (pintype "passive"))
      (node (ref "C3") (pin "1") (pinfunction "1_1") (pintype "passive"))
      (node (ref "C30") (pin "1") (pinfunction "1_1") (pintype "passive"))
      (node (ref "C32") (pin "1") (pinfunction "1_1") (pintype "passive"))
      (node (ref "C4") (pin "P$1") (pinfunction "1_P$1") (pintype "passive"))
      (node (ref "C5") (pin "1") (pinfunction "1_1") (pintype "passive"))
      (node (ref "C6") (pin "1") (pinfunction "1_1") (pintype "passive"))
      (node (ref "C7") (pin "1") (pinfunction "1_1") (pintype "passive"))
      (node (ref "C8") (pin "P$2") (pinfunction "2_P$2") (pintype "passive"))
      (node (ref "C9") (pin "2") (pinfunction "2_2") (pintype "passive"))
      (node (ref "CON1") (pin "6") (pinfunction "6_6") (pintype "passive"))
      (node (ref "CON1") (pin "G1") (pinfunction "G1_G1") (pintype "passive"))
      (node (ref "CON1") (pin "G2") (pinfunction "G2_G2") (pintype "passive"))
      (node (ref "IC1") (pin "10") (pinfunction "PC2_10") (pintype "bidirectional"))
      (node (ref "IC1") (pin "11") (pinfunction "PC3_11") (pintype "bidirectional"))
      (node (ref "IC1") (pin "12") (pinfunction "VSSA_12") (pintype "bidirectional"))
      (node (ref "IC1") (pin "18") (pinfunction "VSS_18") (pintype "bidirectional"))
      (node (ref "IC1") (pin "31") (pinfunction "VSS_31") (pintype "bidirectional"))
      (node (ref "IC1") (pin "47") (pinfunction "VSS_47") (pintype "bidirectional"))
      (node (ref "IC1") (pin "63") (pinfunction "VSS_63") (pintype "bidirectional"))
      (node (ref "IC1") (pin "9") (pinfunction "PC1_9") (pintype "bidirectional"))
      (node (ref "IC2") (pin "2") (pinfunction "VSS_2") (pintype "bidirectional"))
      (node (ref "IC3") (pin "2") (pinfunction "GND_2") (pintype "bidirectional"))
      (node (ref "IC4") (pin "2") (pinfunction "GND_2") (pintype "bidirectional"))
      (node (ref "IC5") (pin "4") (pinfunction "GND_4") (pintype "bidirectional"))
      (node (ref "IC5") (pin "5") (pinfunction "A2_5") (pintype "bidirectional"))
      (node (ref "IC5") (pin "6") (pinfunction "A1_6") (pintype "bidirectional"))
      (node (ref "IC5") (pin "7") (pinfunction "A0_7") (pintype "bidirectional"))
      (node (ref "IC6") (pin "11") (pinfunction "GND_11") (pintype "bidirectional"))
      (node (ref "IC7") (pin "2") (pinfunction "GND_2") (pintype "bidirectional"))
      (node (ref "IC8") (pin "1") (pinfunction "GND_1") (pintype "bidirectional"))
      (node (ref "R1") (pin "2") (pinfunction "2_2") (pintype "passive"))
      (node (ref "R10") (pin "1") (pinfunction "1_1") (pintype "passive"))
      (node (ref "R14") (pin "CURRENT2") (pinfunction "C2_CURRENT2") (pintype "bidirectional"))
      (node (ref "R15") (pin "1") (pinfunction "1_1") (pintype "passive"))
      (node (ref "R19") (pin "1") (pinfunction "1_1") (pintype "passive"))
      (node (ref "R4") (pin "1") (pinfunction "1_1") (pintype "passive"))
      (node (ref "R8") (pin "2") (pinfunction "2_2") (pintype "passive"))
      (node (ref "TP3") (pin "P$1") (pinfunction "P$1_P$1") (pintype "passive"))
      (node (ref "U$2") (pin "P$2") (pinfunction "P$2_P$2") (pintype "bidirectional"))
      (node (ref "X1") (pin "2") (pinfunction "GND_2") (pintype "bidirectional"))
      (node (ref "X1") (pin "4") (pinfunction "GND_4") (pintype "bidirectional"))
    )
    (net (code "25") (name "GNDD") (class "Default")
      (node (ref "CON2") (pin "4") (pinfunction "4_4") (pintype "bidirectional"))
      (node (ref "CON2") (pin "M$0") (pinfunction "GND_M$0") (pintype "bidirectional"))
      (node (ref "CON2") (pin "M$1") (pinfunction "GND_M$1") (pintype "bidirectional"))
      (node (ref "CON3") (pin "4") (pinfunction "4_4") (pintype "bidirectional"))
      (node (ref "CON3") (pin "M$0") (pinfunction "GND_M$0") (pintype "bidirectional"))
      (node (ref "CON3") (pin "M$1") (pinfunction "GND_M$1") (pintype "bidirectional"))
      (node (ref "CON4") (pin "4") (pinfunction "4_4") (pintype "bidirectional"))
      (node (ref "CON4") (pin "M$0") (pinfunction "GND_M$0") (pintype "bidirectional"))
      (node (ref "CON4") (pin "M$1") (pinfunction "GND_M$1") (pintype "bidirectional"))
      (node (ref "CON5") (pin "4") (pinfunction "4_4") (pintype "bidirectional"))
      (node (ref "CON5") (pin "M$0") (pinfunction "GND_M$0") (pintype "bidirectional"))
      (node (ref "CON5") (pin "M$1") (pinfunction "GND_M$1") (pintype "bidirectional"))
      (node (ref "U$2") (pin "P$1") (pinfunction "P$1_P$1") (pintype "bidirectional"))
    )
    (net (code "26") (name "I2C_SCL") (class "Default")
      (node (ref "IC1") (pin "61") (pinfunction "PB8_61") (pintype "bidirectional"))
      (node (ref "IC2") (pin "1") (pinfunction "SCL_1") (pintype "bidirectional"))
      (node (ref "IC5") (pin "2") (pinfunction "SCL_2") (pintype "bidirectional"))
      (node (ref "R3") (pin "2") (pinfunction "2_2") (pintype "passive"))
    )
    (net (code "27") (name "I2C_SDA") (class "Default")
      (node (ref "IC1") (pin "62") (pinfunction "PB9_62") (pintype "bidirectional"))
      (node (ref "IC2") (pin "3") (pinfunction "SDA_3") (pintype "bidirectional"))
      (node (ref "IC5") (pin "1") (pinfunction "SDA_1") (pintype "bidirectional"))
      (node (ref "R2") (pin "2") (pinfunction "2_2") (pintype "passive"))
    )
    (net (code "28") (name "Net-(CON1-Pad2)") (class "Default")
      (node (ref "CON1") (pin "2") (pinfunction "2_2") (pintype "passive"))
      (node (ref "R5") (pin "1") (pinfunction "1_1") (pintype "passive"))
    )
    (net (code "29") (name "Net-(CON1-Pad3)") (class "Default")
      (node (ref "CON1") (pin "3") (pinfunction "3_3") (pintype "passive"))
      (node (ref "R6") (pin "1") (pinfunction "1_1") (pintype "passive"))
    )
    (net (code "30") (name "Net-(CON2-Pad1)") (class "Default")
      (node (ref "CON2") (pin "1") (pinfunction "1_1") (pintype "bidirectional"))
      (node (ref "CON3") (pin "1") (pinfunction "1_1") (pintype "bidirectional"))
    )
    (net (code "31") (name "Net-(CON4-Pad1)") (class "Default")
      (node (ref "CON4") (pin "1") (pinfunction "1_1") (pintype "bidirectional"))
      (node (ref "CON5") (pin "1") (pinfunction "1_1") (pintype "bidirectional"))
    )
    (net (code "32") (name "Net-(IC1-BOOT0)") (class "Default")
      (node (ref "IC1") (pin "60") (pinfunction "BOOT0_60") (pintype "bidirectional"))
      (node (ref "R4") (pin "2") (pinfunction "2_2") (pintype "passive"))
    )
    (net (code "33") (name "Net-(IC1-PB15)") (class "Default")
      (node (ref "IC1") (pin "36") (pinfunction "PB15_36") (pintype "bidirectional"))
      (node (ref "TP5") (pin "P$1") (pinfunction "P$1_P$1") (pintype "passive"))
    )
    (net (code "34") (name "Net-(IC1-PC0)") (class "Default")
      (node (ref "IC1") (pin "8") (pinfunction "PC0_8") (pintype "bidirectional"))
      (node (ref "R1") (pin "1") (pinfunction "1_1") (pintype "passive"))
    )
    (net (code "35") (name "Net-(IC1-PC6)") (class "Default")
      (node (ref "IC1") (pin "37") (pinfunction "PC6_37") (pintype "bidirectional"))
      (node (ref "R25") (pin "2") (pinfunction "2_2") (pintype "passive"))
    )
    (net (code "36") (name "Net-(IC1-PC7)") (class "Default")
      (node (ref "IC1") (pin "38") (pinfunction "PC7_38") (pintype "bidirectional"))
      (node (ref "R24") (pin "2") (pinfunction "2_2") (pintype "passive"))
    )
    (net (code "37") (name "Net-(IC1-PC8)") (class "Default")
      (node (ref "IC1") (pin "39") (pinfunction "PC8_39") (pintype "bidirectional"))
      (node (ref "R23") (pin "2") (pinfunction "2_2") (pintype "passive"))
    )
    (net (code "38") (name "Net-(IC1-PC11)") (class "Default")
      (node (ref "IC1") (pin "52") (pinfunction "PC11_52") (pintype "bidirectional"))
      (node (ref "TP1") (pin "P$1") (pinfunction "P$1_P$1") (pintype "passive"))
    )
    (net (code "39") (name "Net-(IC1-PC12)") (class "Default")
      (node (ref "IC1") (pin "53") (pinfunction "PC12_53") (pintype "bidirectional"))
      (node (ref "TP2") (pin "P$1") (pinfunction "P$1_P$1") (pintype "passive"))
    )
    (net (code "40") (name "Net-(IC1-PD0)") (class "Default")
      (node (ref "C1") (pin "2") (pinfunction "2_2") (pintype "passive"))
      (node (ref "IC1") (pin "5") (pinfunction "PD0_5") (pintype "bidirectional"))
      (node (ref "X1") (pin "3") (pinfunction "2_3") (pintype "passive"))
    )
    (net (code "41") (name "Net-(IC1-PD1)") (class "Default")
      (node (ref "C2") (pin "2") (pinfunction "2_2") (pintype "passive"))
      (node (ref "IC1") (pin "6") (pinfunction "PD1_6") (pintype "bidirectional"))
      (node (ref "X1") (pin "1") (pinfunction "1_1") (pintype "passive"))
    )
    (net (code "42") (name "Net-(IC2-WP)") (class "Default")
      (node (ref "IC2") (pin "5") (pinfunction "WP_5") (pintype "bidirectional"))
      (node (ref "R26") (pin "2") (pinfunction "2_2") (pintype "passive"))
    )
    (net (code "43") (name "Net-(IC3-CANH)") (class "Default")
      (node (ref "CON2") (pin "2") (pinfunction "2_2") (pintype "bidirectional"))
      (node (ref "CON3") (pin "2") (pinfunction "2_2") (pintype "bidirectional"))
      (node (ref "IC3") (pin "7") (pinfunction "CANH_7") (pintype "bidirectional"))
    )
    (net (code "44") (name "Net-(IC3-CANL)") (class "Default")
      (node (ref "CON2") (pin "3") (pinfunction "3_3") (pintype "bidirectional"))
      (node (ref "CON3") (pin "3") (pinfunction "3_3") (pintype "bidirectional"))
      (node (ref "IC3") (pin "6") (pinfunction "CANL_6") (pintype "bidirectional"))
    )
    (net (code "45") (name "Net-(IC4-CANH)") (class "Default")
      (node (ref "CON4") (pin "2") (pinfunction "2_2") (pintype "bidirectional"))
      (node (ref "CON5") (pin "2") (pinfunction "2_2") (pintype "bidirectional"))
      (node (ref "IC4") (pin "7") (pinfunction "CANH_7") (pintype "bidirectional"))
    )
    (net (code "46") (name "Net-(IC4-CANL)") (class "Default")
      (node (ref "CON4") (pin "3") (pinfunction "3_3") (pintype "bidirectional"))
      (node (ref "CON5") (pin "3") (pinfunction "3_3") (pintype "bidirectional"))
      (node (ref "IC4") (pin "6") (pinfunction "CANL_6") (pintype "bidirectional"))
    )
    (net (code "47") (name "Net-(IC7-VOUT)") (class "Default")
      (node (ref "IC7") (pin "3") (pinfunction "VOUT_3") (pintype "bidirectional"))
      (node (ref "R7") (pin "1") (pinfunction "1_1") (pintype "passive"))
    )
    (net (code "48") (name "Net-(IC7-VSENSE+)") (class "Default")
      (node (ref "IC7") (pin "4") (pinfunction "VSENSE+_4") (pintype "bidirectional"))
      (node (ref "R14") (pin "SENSE1") (pinfunction "S1_SENSE1") (pintype "bidirectional"))
    )
    (net (code "49") (name "Net-(IC7-VSENSE-)") (class "Default")
      (node (ref "IC7") (pin "5") (pinfunction "VSENSE-_5") (pintype "bidirectional"))
      (node (ref "R14") (pin "SENSE2") (pinfunction "S2_SENSE2") (pintype "bidirectional"))
    )
    (net (code "50") (name "Net-(LED1-PadB)") (class "Default")
      (node (ref "LED1") (pin "B") (pinfunction "B_B") (pintype "bidirectional"))
      (node (ref "R23") (pin "1") (pinfunction "1_1") (pintype "passive"))
    )
    (net (code "51") (name "Net-(LED1-PadG)") (class "Default")
      (node (ref "LED1") (pin "G") (pinfunction "G_G") (pintype "bidirectional"))
      (node (ref "R24") (pin "1") (pinfunction "1_1") (pintype "passive"))
    )
    (net (code "52") (name "Net-(LED1-PadR)") (class "Default")
      (node (ref "LED1") (pin "R") (pinfunction "R_R") (pintype "bidirectional"))
      (node (ref "R25") (pin "1") (pinfunction "1_1") (pintype "passive"))
    )
    (net (code "53") (name "Net-(Q1-G)") (class "Default")
      (node (ref "Q1") (pin "4G") (pinfunction "G_4G") (pintype "passive"))
      (node (ref "R11") (pin "1") (pinfunction "1_1") (pintype "passive"))
    )
    (net (code "54") (name "Net-(Q2-G)") (class "Default")
      (node (ref "Q2") (pin "4G") (pinfunction "G_4G") (pintype "passive"))
      (node (ref "R12") (pin "1") (pinfunction "1_1") (pintype "passive"))
    )
    (net (code "55") (name "Net-(Q3-G)") (class "Default")
      (node (ref "Q3") (pin "4G") (pinfunction "G_4G") (pintype "passive"))
      (node (ref "R16") (pin "1") (pinfunction "1_1") (pintype "passive"))
    )
    (net (code "56") (name "Net-(Q4-G)") (class "Default")
      (node (ref "Q4") (pin "4G") (pinfunction "G_4G") (pintype "passive"))
      (node (ref "R17") (pin "1") (pinfunction "1_1") (pintype "passive"))
    )
    (net (code "57") (name "Net-(Q5-G)") (class "Default")
      (node (ref "Q5") (pin "4G") (pinfunction "G_4G") (pintype "passive"))
      (node (ref "R20") (pin "1") (pinfunction "1_1") (pintype "passive"))
    )
    (net (code "58") (name "Net-(Q6-G)") (class "Default")
      (node (ref "Q6") (pin "4G") (pinfunction "G_4G") (pintype "passive"))
      (node (ref "R21") (pin "1") (pinfunction "1_1") (pintype "passive"))
    )
    (net (code "59") (name "SENSE_A") (class "Default")
      (node (ref "C24") (pin "2") (pinfunction "2_2") (pintype "passive"))
      (node (ref "IC1") (pin "15") (pinfunction "PA1_15") (pintype "bidirectional"))
      (node (ref "R10") (pin "2") (pinfunction "2_2") (pintype "passive"))
      (node (ref "R13") (pin "2") (pinfunction "2_2") (pintype "passive"))
    )
    (net (code "60") (name "SENSE_B") (class "Default")
      (node (ref "C30") (pin "2") (pinfunction "2_2") (pintype "passive"))
      (node (ref "IC1") (pin "16") (pinfunction "PA2_16") (pintype "bidirectional"))
      (node (ref "R15") (pin "2") (pinfunction "2_2") (pintype "passive"))
      (node (ref "R18") (pin "2") (pinfunction "2_2") (pintype "passive"))
    )
    (net (code "61") (name "SENSE_C") (class "Default")
      (node (ref "C32") (pin "2") (pinfunction "2_2") (pintype "passive"))
      (node (ref "IC1") (pin "17") (pinfunction "PA3_17") (pintype "bidirectional"))
      (node (ref "R19") (pin "2") (pinfunction "2_2") (pintype "passive"))
      (node (ref "R22") (pin "2") (pinfunction "2_2") (pintype "passive"))
    )
    (net (code "62") (name "SENSE_CURRENT") (class "Default")
      (node (ref "C28") (pin "P$2") (pinfunction "2_P$2") (pintype "passive"))
      (node (ref "IC1") (pin "21") (pinfunction "PA5_21") (pintype "bidirectional"))
      (node (ref "R7") (pin "2") (pinfunction "2_2") (pintype "passive"))
    )
    (net (code "63") (name "SENSE_VIN") (class "Default")
      (node (ref "C15") (pin "2") (pinfunction "2_2") (pintype "passive"))
      (node (ref "IC1") (pin "20") (pinfunction "PA4_20") (pintype "bidirectional"))
      (node (ref "R8") (pin "1") (pinfunction "1_1") (pintype "passive"))
      (node (ref "R9") (pin "1") (pinfunction "1_1") (pintype "passive"))
    )
    (net (code "64") (name "SWCLK") (class "Default")
      (node (ref "CON1") (pin "5") (pinfunction "5_5") (pintype "passive"))
      (node (ref "IC1") (pin "49") (pinfunction "PA14_49") (pintype "bidirectional"))
    )
    (net (code "65") (name "SWDIO") (class "Default")
      (node (ref "CON1") (pin "4") (pinfunction "4_4") (pintype "passive"))
      (node (ref "IC1") (pin "46") (pinfunction "PA13_46") (pintype "bidirectional"))
    )
    (net (code "66") (name "TSENS_OS") (class "Default")
      (node (ref "IC1") (pin "56") (pinfunction "PB4_56") (pintype "bidirectional"))
      (node (ref "IC5") (pin "3") (pinfunction "OS_3") (pintype "bidirectional"))
    )
    (net (code "67") (name "USART1_RX{slash}PWM") (class "Default")
      (node (ref "IC1") (pin "14") (pinfunction "PA0-WKUP_14") (pintype "bidirectional"))
      (node (ref "IC1") (pin "59") (pinfunction "PB7_59") (pintype "bidirectional"))
      (node (ref "R6") (pin "2") (pinfunction "2_2") (pintype "passive"))
    )
    (net (code "68") (name "USART1_TX") (class "Default")
      (node (ref "IC1") (pin "58") (pinfunction "PB6_58") (pintype "bidirectional"))
      (node (ref "R5") (pin "2") (pinfunction "2_2") (pintype "passive"))
    )
    (net (code "69") (name "VBAT") (class "Default")
      (node (ref "B+") (pin "1") (pinfunction "P_1") (pintype "passive"))
      (node (ref "C14") (pin "1") (pinfunction "1_1") (pintype "passive"))
      (node (ref "C16") (pin "P$2") (pinfunction "2_P$2") (pintype "passive"))
      (node (ref "C17") (pin "P$2") (pinfunction "2_P$2") (pintype "passive"))
      (node (ref "C18") (pin "P$2") (pinfunction "2_P$2") (pintype "passive"))
      (node (ref "C19") (pin "P$2") (pinfunction "2_P$2") (pintype "passive"))
      (node (ref "C20") (pin "P$2") (pinfunction "2_P$2") (pintype "passive"))
      (node (ref "C21") (pin "P$2") (pinfunction "2_P$2") (pintype "passive"))
      (node (ref "C22") (pin "P$2") (pinfunction "2_P$2") (pintype "passive"))
      (node (ref "C23") (pin "P$2") (pinfunction "2_P$2") (pintype "passive"))
      (node (ref "C25") (pin "P$2") (pinfunction "2_P$2") (pintype "passive"))
      (node (ref "C26") (pin "P$2") (pinfunction "2_P$2") (pintype "passive"))
      (node (ref "C27") (pin "P$1") (pinfunction "1_P$1") (pintype "passive"))
      (node (ref "C35") (pin "+") (pinfunction "+_+") (pintype "passive"))
      (node (ref "D3") (pin "A") (pinfunction "A_A") (pintype "passive"))
      (node (ref "D4") (pin "A") (pinfunction "A_A") (pintype "passive"))
      (node (ref "D5") (pin "A") (pinfunction "A_A") (pintype "passive"))
      (node (ref "D6") (pin "C") (pinfunction "C_C") (pintype "bidirectional"))
      (node (ref "IC6") (pin "12") (pinfunction "VDD_12") (pintype "bidirectional"))
      (node (ref "IC8") (pin "3") (pinfunction "IN_3") (pintype "bidirectional"))
      (node (ref "Q1") (pin "5D") (pinfunction "D_5D") (pintype "passive"))
      (node (ref "Q1") (pin "6D") (pinfunction "D_6D") (pintype "passive"))
      (node (ref "Q1") (pin "7D") (pinfunction "D_7D") (pintype "passive"))
      (node (ref "Q1") (pin "8D") (pinfunction "D_8D") (pintype "passive"))
      (node (ref "Q3") (pin "5D") (pinfunction "D_5D") (pintype "passive"))
      (node (ref "Q3") (pin "6D") (pinfunction "D_6D") (pintype "passive"))
      (node (ref "Q3") (pin "7D") (pinfunction "D_7D") (pintype "passive"))
      (node (ref "Q3") (pin "8D") (pinfunction "D_8D") (pintype "passive"))
      (node (ref "Q5") (pin "5D") (pinfunction "D_5D") (pintype "passive"))
      (node (ref "Q5") (pin "6D") (pinfunction "D_6D") (pintype "passive"))
      (node (ref "Q5") (pin "7D") (pinfunction "D_7D") (pintype "passive"))
      (node (ref "Q5") (pin "8D") (pinfunction "D_8D") (pintype "passive"))
      (node (ref "R9") (pin "2") (pinfunction "2_2") (pintype "passive"))
    )
    (net (code "70") (name "VDD_3V3") (class "Default")
      (node (ref "C10") (pin "1") (pinfunction "1_1") (pintype "passive"))
      (node (ref "C11") (pin "1") (pinfunction "1_1") (pintype "passive"))
      (node (ref "C12") (pin "1") (pinfunction "1_1") (pintype "passive"))
      (node (ref "C13") (pin "1") (pinfunction "1_1") (pintype "passive"))
      (node (ref "C29") (pin "P$2") (pinfunction "2_P$2") (pintype "passive"))
      (node (ref "C3") (pin "2") (pinfunction "2_2") (pintype "passive"))
      (node (ref "C4") (pin "P$2") (pinfunction "2_P$2") (pintype "passive"))
      (node (ref "C5") (pin "2") (pinfunction "2_2") (pintype "passive"))
      (node (ref "C6") (pin "2") (pinfunction "2_2") (pintype "passive"))
      (node (ref "C7") (pin "2") (pinfunction "2_2") (pintype "passive"))
      (node (ref "C8") (pin "P$1") (pinfunction "1_P$1") (pintype "passive"))
      (node (ref "C9") (pin "1") (pinfunction "1_1") (pintype "passive"))
      (node (ref "CON1") (pin "1") (pinfunction "1_1") (pintype "passive"))
      (node (ref "IC1") (pin "1") (pinfunction "VBAT_1") (pintype "bidirectional"))
      (node (ref "IC1") (pin "13") (pinfunction "VDDA_13") (pintype "bidirectional"))
      (node (ref "IC1") (pin "19") (pinfunction "VDD_19") (pintype "bidirectional"))
      (node (ref "IC1") (pin "32") (pinfunction "VDD_32") (pintype "bidirectional"))
      (node (ref "IC1") (pin "48") (pinfunction "VDD_48") (pintype "bidirectional"))
      (node (ref "IC1") (pin "64") (pinfunction "VDD_64") (pintype "bidirectional"))
      (node (ref "IC2") (pin "4") (pinfunction "VCC_4") (pintype "bidirectional"))
      (node (ref "IC3") (pin "3") (pinfunction "VCC_3") (pintype "bidirectional"))
      (node (ref "IC4") (pin "3") (pinfunction "VCC_3") (pintype "bidirectional"))
      (node (ref "IC5") (pin "8") (pinfunction "VCC_8") (pintype "bidirectional"))
      (node (ref "IC7") (pin "1") (pinfunction "VCC_1") (pintype "bidirectional"))
      (node (ref "IC8") (pin "2") (pinfunction "OUT_2") (pintype "bidirectional"))
      (node (ref "IC8") (pin "4") (pinfunction "OUT_4") (pintype "bidirectional"))
      (node (ref "LED1") (pin "+") (pinfunction "A_+") (pintype "bidirectional"))
      (node (ref "R2") (pin "1") (pinfunction "1_1") (pintype "passive"))
      (node (ref "R26") (pin "1") (pinfunction "1_1") (pintype "passive"))
      (node (ref "R3") (pin "1") (pinfunction "1_1") (pintype "passive"))
      (node (ref "TP4") (pin "P$1") (pinfunction "P$1_P$1") (pintype "passive"))
    )
    (net (code "71") (name "unconnected-(IC1-NRST-Pad7)") (class "Default")
      (node (ref "IC1") (pin "7") (pinfunction "NRST_7") (pintype "bidirectional"))
    )
    (net (code "72") (name "unconnected-(IC1-PA6-Pad22)") (class "Default")
      (node (ref "IC1") (pin "22") (pinfunction "PA6_22") (pintype "bidirectional"))
    )
    (net (code "73") (name "unconnected-(IC1-PA15-Pad50)") (class "Default")
      (node (ref "IC1") (pin "50") (pinfunction "PA15_50") (pintype "bidirectional"))
    )
    (net (code "74") (name "unconnected-(IC1-PB2-Pad28)") (class "Default")
      (node (ref "IC1") (pin "28") (pinfunction "PB2_28") (pintype "bidirectional"))
    )
    (net (code "75") (name "unconnected-(IC1-PB3-Pad55)") (class "Default")
      (node (ref "IC1") (pin "55") (pinfunction "PB3_55") (pintype "bidirectional"))
    )
    (net (code "76") (name "unconnected-(IC1-PB5-Pad57)") (class "Default")
      (node (ref "IC1") (pin "57") (pinfunction "PB5_57") (pintype "bidirectional"))
    )
    (net (code "77") (name "unconnected-(IC1-PB10-Pad29)") (class "Default")
      (node (ref "IC1") (pin "29") (pinfunction "PB10_29") (pintype "bidirectional"))
    )
    (net (code "78") (name "unconnected-(IC1-PB11-Pad30)") (class "Default")
      (node (ref "IC1") (pin "30") (pinfunction "PB11_30") (pintype "bidirectional"))
    )
    (net (code "79") (name "unconnected-(IC1-PB14-Pad35)") (class "Default")
      (node (ref "IC1") (pin "35") (pinfunction "PB14_35") (pintype "bidirectional"))
    )
    (net (code "80") (name "unconnected-(IC1-PC4-Pad24)") (class "Default")
      (node (ref "IC1") (pin "24") (pinfunction "PC4_24") (pintype "bidirectional"))
    )
    (net (code "81") (name "unconnected-(IC1-PC5-Pad25)") (class "Default")
      (node (ref "IC1") (pin "25") (pinfunction "PC5_25") (pintype "bidirectional"))
    )
    (net (code "82") (name "unconnected-(IC1-PC9-Pad40)") (class "Default")
      (node (ref "IC1") (pin "40") (pinfunction "PC9_40") (pintype "bidirectional"))
    )
    (net (code "83") (name "unconnected-(IC1-PC10-Pad51)") (class "Default")
      (node (ref "IC1") (pin "51") (pinfunction "PC10_51") (pintype "bidirectional"))
    )
    (net (code "84") (name "unconnected-(IC1-PC13-Pad2)") (class "Default")
      (node (ref "IC1") (pin "2") (pinfunction "PC13_2") (pintype "bidirectional"))
    )
    (net (code "85") (name "unconnected-(IC1-PC14-Pad3)") (class "Default")
      (node (ref "IC1") (pin "3") (pinfunction "PC14_3") (pintype "bidirectional"))
    )
    (net (code "86") (name "unconnected-(IC1-PC15-Pad4)") (class "Default")
      (node (ref "IC1") (pin "4") (pinfunction "PC15_4") (pintype "bidirectional"))
    )
    (net (code "87") (name "unconnected-(IC1-PD2-Pad54)") (class "Default")
      (node (ref "IC1") (pin "54") (pinfunction "PD2_54") (pintype "bidirectional"))
    )
    (net (code "88") (name "unconnected-(IC3-NC-Pad5)") (class "Default")
      (node (ref "IC3") (pin "5") (pinfunction "NC_5") (pintype "bidirectional"))
    )
    (net (code "89") (name "unconnected-(IC3-NC-Pad8)") (class "Default")
      (node (ref "IC3") (pin "8") (pinfunction "NC_8") (pintype "bidirectional"))
    )
    (net (code "90") (name "unconnected-(IC4-NC-Pad5)") (class "Default")
      (node (ref "IC4") (pin "5") (pinfunction "NC_5") (pintype "bidirectional"))
    )
    (net (code "91") (name "unconnected-(IC4-NC-Pad8)") (class "Default")
      (node (ref "IC4") (pin "8") (pinfunction "NC_8") (pintype "bidirectional"))
    )
  )
)
